# I2S_Mic.net
KiCad netlist of a schematic drawn in Altium Designer
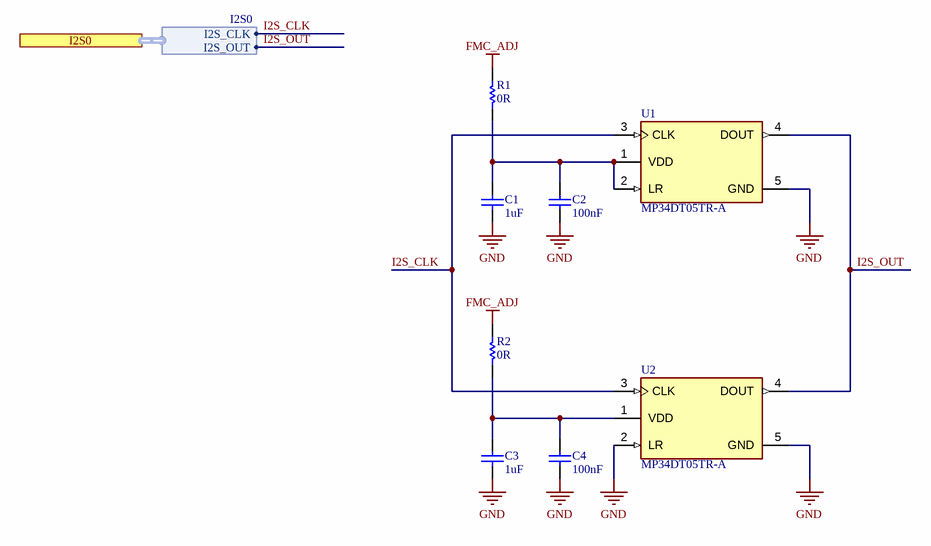
[diagram p0: I2S_Mic.SchDoc]

(export (version "E")
  (design (tool "Eeschema 10.0.6"))
  (components
    (comp (ref "C1")
      (value "1uF")
      (footprint "CAPC1005X60X30LL05T10")
      (fields
        (field (name "PART NUMBER") "C0402C105K9PACTU")
        (field (name "MANUFACTURER") "Kemet")
        (field (name "TOLERANCE") "10%")
      )
      (libsource (lib "Altium Content Vault") (part "CAP"))
    )
    (comp (ref "C2")
      (value "100nF")
      (footprint "CAPC1050X55X23LL05T13")
      (description "Chip Capacitor, 100 nF, +/- 10%, 16 V, -55 to 125 degC, 0402 (1005 Metric), RoHS, Tape and Reel")
      (fields
        (field (name "MANUFACTURER") "Samsung Electro-Mechanics")
        (field (name "MANUFACTURER PART NUMBER") "CL05B104KO5NNNC")
      )
      (libsource (lib "Altium Content Vault") (part "CAP-NP-2"))
    )
    (comp (ref "C3")
      (value "1uF")
      (footprint "CAPC1005X60X30LL05T10")
      (fields
        (field (name "PART NUMBER") "C0402C105K9PACTU")
        (field (name "MANUFACTURER") "Kemet")
        (field (name "TOLERANCE") "10%")
      )
      (libsource (lib "Altium Content Vault") (part "CAP"))
    )
    (comp (ref "C4")
      (value "100nF")
      (footprint "CAPC1050X55X23LL05T13")
      (description "Chip Capacitor, 100 nF, +/- 10%, 16 V, -55 to 125 degC, 0402 (1005 Metric), RoHS, Tape and Reel")
      (fields
        (field (name "MANUFACTURER") "Samsung Electro-Mechanics")
        (field (name "MANUFACTURER PART NUMBER") "CL05B104KO5NNNC")
      )
      (libsource (lib "Altium Content Vault") (part "CAP-NP-2"))
    )
    (comp (ref "R1")
      (value "0R")
      (footprint "RESC1005X40X25LL05T10")
      (fields
        (field (name "MANUFACTURER") "Yageo")
        (field (name "PART NUMBER") "RC0402JR-070RL")
        (field (name "TOLERANCE") "5%")
      )
      (libsource (lib "Altium Content Vault") (part "RES"))
    )
    (comp (ref "R2")
      (value "0R")
      (footprint "RESC1005X40X25LL05T10")
      (fields
        (field (name "MANUFACTURER") "Yageo")
        (field (name "PART NUMBER") "RC0402JR-070RL")
        (field (name "TOLERANCE") "5%")
      )
      (libsource (lib "Altium Content Vault") (part "RES"))
    )
    (comp (ref "U1")
      (value "MP34DT05TR-A")
      (footprint "FP-HCLGA-DM00231908-MFG")
      (description "MEMS AUD MIC SENSOR OMNI 4HCLGA")
      (fields
        (field (name "OCTOPART") "https://octopart.com/mp34dt05tr-a-stmicroelectronics-87879016")
        (field (name "MANUFACTURER") "STMicroelectronics")
      )
      (libsource (lib "Altium Content Vault") (part "b42018b50dcec9466a4e70146be022e"))
    )
    (comp (ref "U2")
      (value "MP34DT05TR-A")
      (footprint "FP-HCLGA-DM00231908-MFG")
      (description "MEMS AUD MIC SENSOR OMNI 4HCLGA")
      (fields
        (field (name "OCTOPART") "https://octopart.com/mp34dt05tr-a-stmicroelectronics-87879016")
        (field (name "MANUFACTURER") "STMicroelectronics")
      )
      (libsource (lib "Altium Content Vault") (part "b42018b50dcec9466a4e70146be022e"))
    )
  )
  (nets
    (net (code "2") (name "/I2S_CLK") (class "Default")
      (node (ref "U1") (pin "3") (pinfunction "CLK_3") (pintype "input"))
      (node (ref "U2") (pin "3") (pinfunction "CLK_3") (pintype "input"))
    )
    (net (code "3") (name "/I2S_OUT") (class "Default")
      (node (ref "U1") (pin "4") (pinfunction "DOUT_4") (pintype "output"))
      (node (ref "U2") (pin "4") (pinfunction "DOUT_4") (pintype "output"))
    )
    (net (code "5") (name "FMC_ADJ") (class "Default")
      (node (ref "R1") (pin "2") (pinfunction "2_2") (pintype "passive"))
      (node (ref "R2") (pin "2") (pinfunction "2_2") (pintype "passive"))
    )
    (net (code "6") (name "GND") (class "Default")
      (node (ref "C1") (pin "1") (pinfunction "1_1") (pintype "passive"))
      (node (ref "C2") (pin "1") (pinfunction "1_1") (pintype "passive"))
      (node (ref "C3") (pin "1") (pinfunction "1_1") (pintype "passive"))
      (node (ref "C4") (pin "1") (pinfunction "1_1") (pintype "passive"))
      (node (ref "U1") (pin "5") (pinfunction "GND_5") (pintype "power_in"))
      (node (ref "U2") (pin "2") (pinfunction "LR_2") (pintype "input"))
      (node (ref "U2") (pin "5") (pinfunction "GND_5") (pintype "power_in"))
    )
    (net (code "7") (name "Net-(U1-LR)") (class "Default")
      (node (ref "C1") (pin "2") (pinfunction "2_2") (pintype "passive"))
      (node (ref "C2") (pin "2") (pinfunction "2_2") (pintype "passive"))
      (node (ref "R1") (pin "1") (pinfunction "1_1") (pintype "passive"))
      (node (ref "U1") (pin "1") (pinfunction "VDD_1") (pintype "power_in"))
      (node (ref "U1") (pin "2") (pinfunction "LR_2") (pintype "input"))
    )
    (net (code "8") (name "Net-(U2-VDD)") (class "Default")
      (node (ref "C3") (pin "2") (pinfunction "2_2") (pintype "passive"))
      (node (ref "C4") (pin "2") (pinfunction "2_2") (pintype "passive"))
      (node (ref "R2") (pin "1") (pinfunction "1_1") (pintype "passive"))
      (node (ref "U2") (pin "1") (pinfunction "VDD_1") (pintype "power_in"))
    )
  )
)
